# Sheet1asc2.net
KiCad netlist of a schematic drawn in Altium Designer
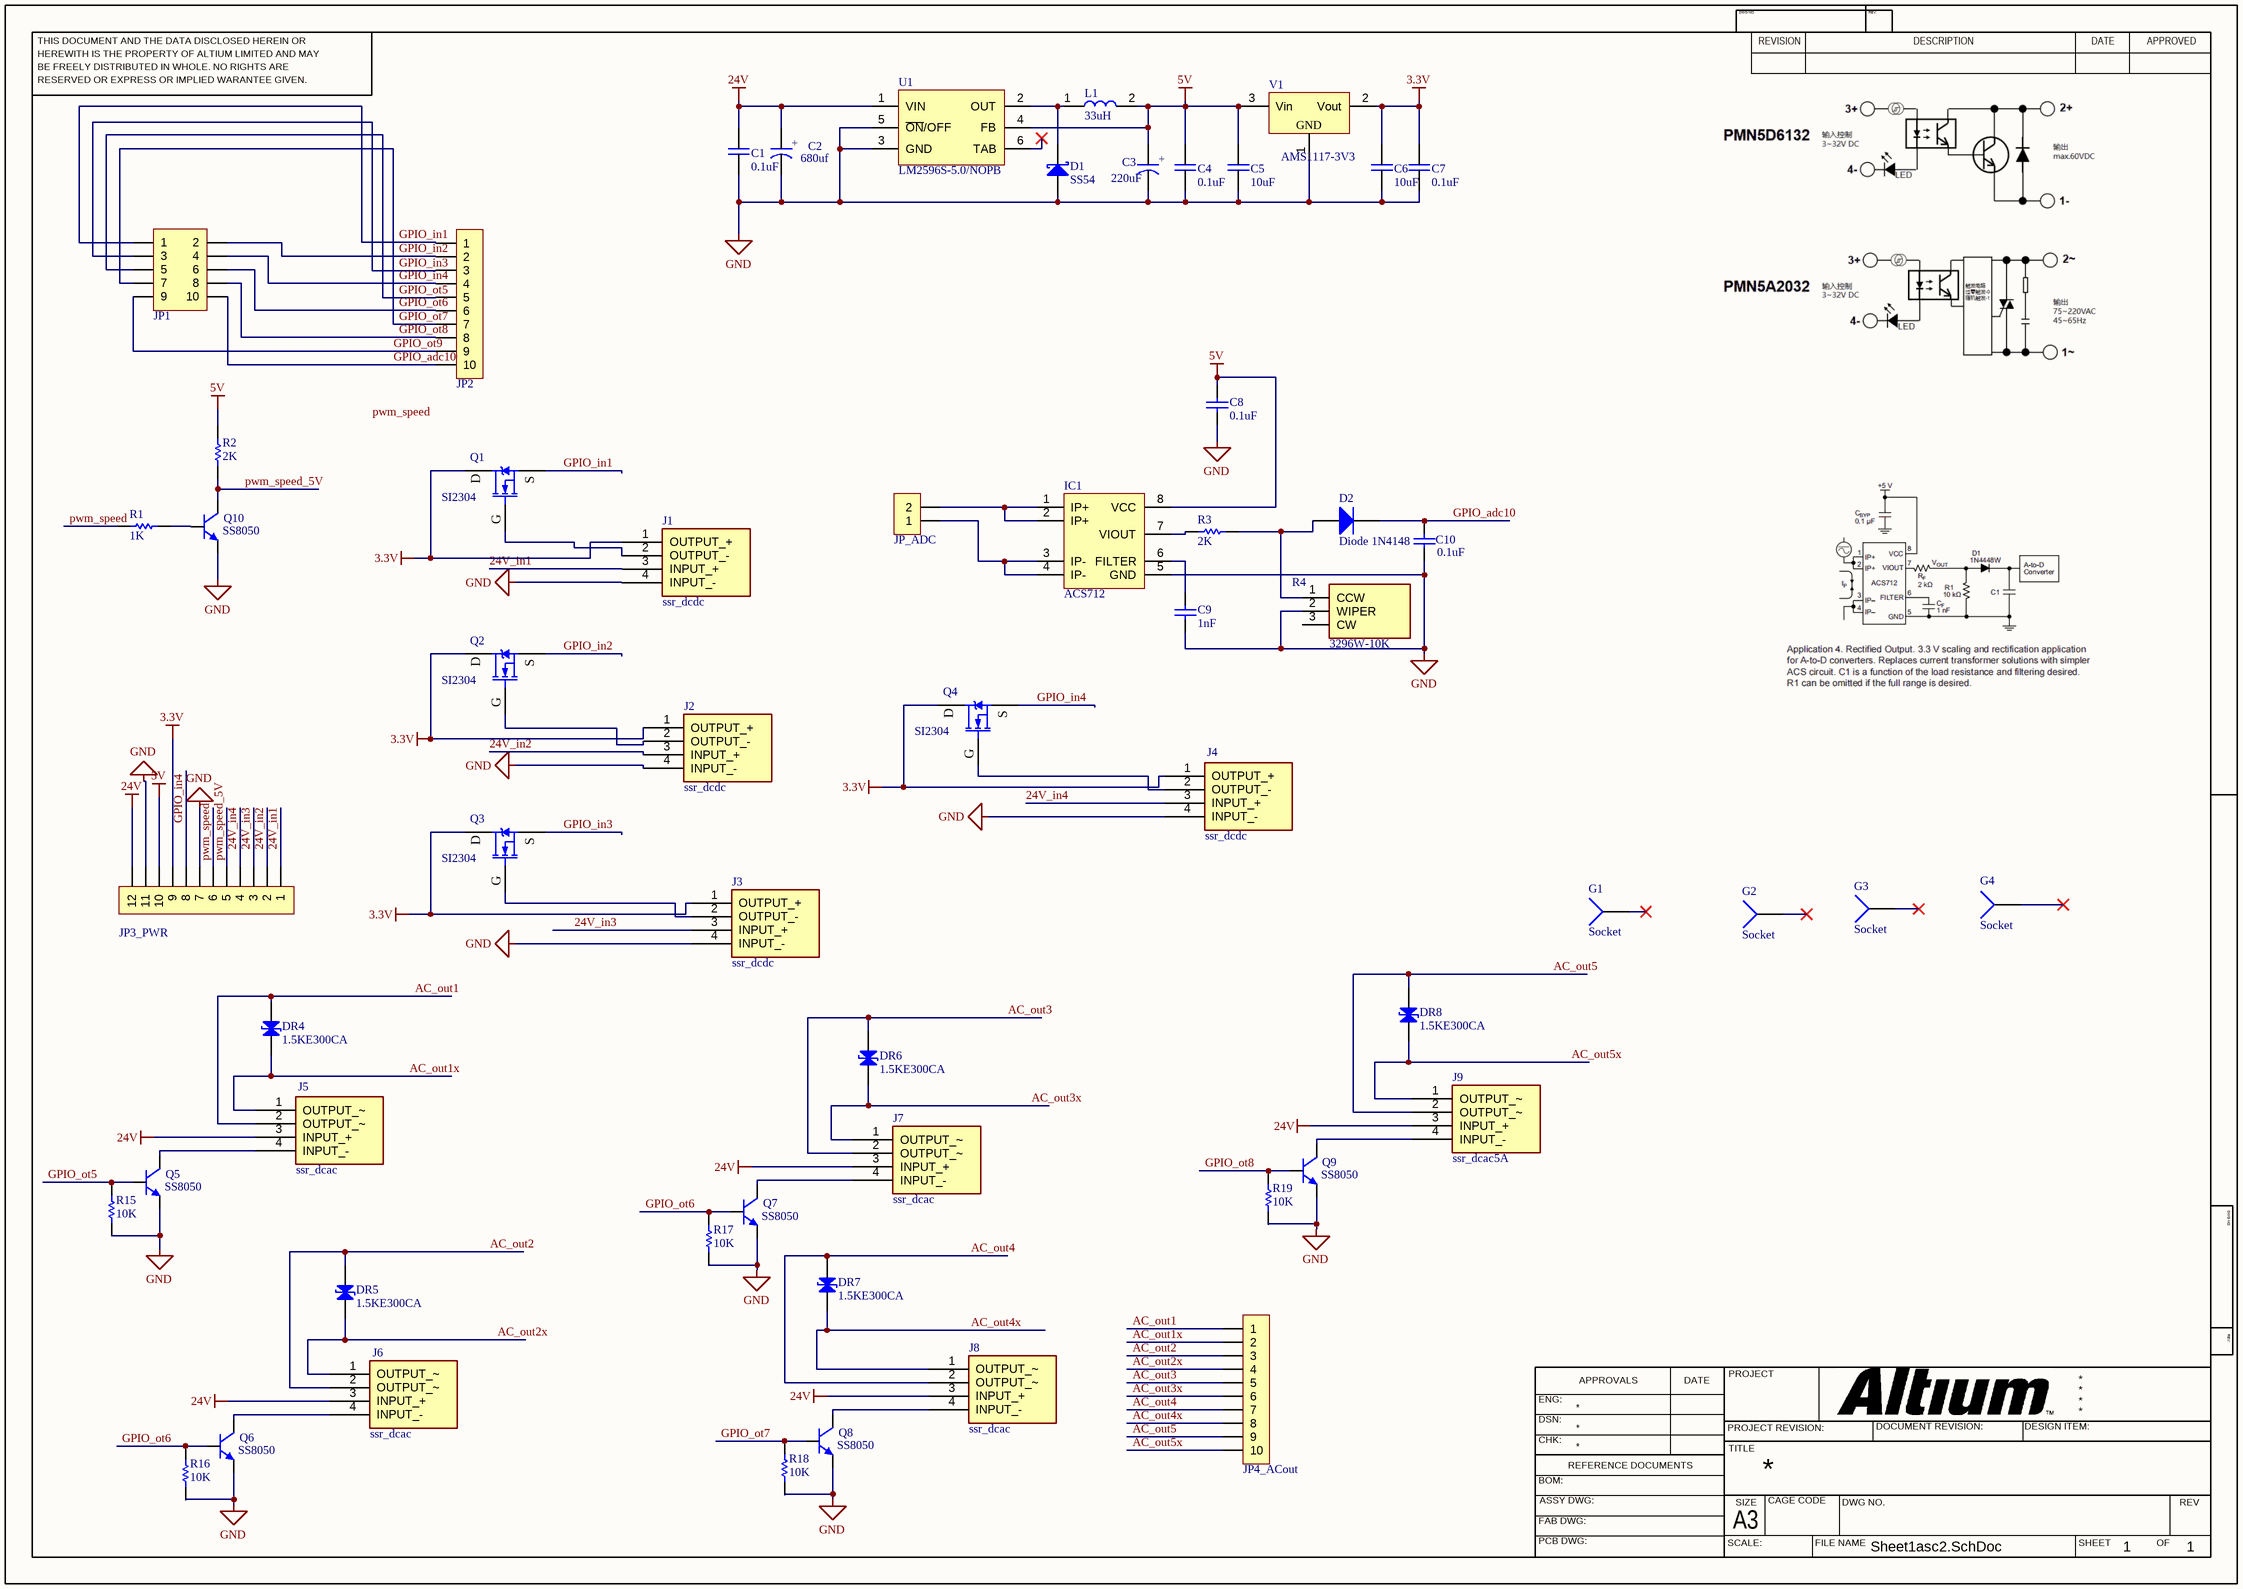
[diagram p0: Sheet1asc2.SchDoc]

(export (version "E")
  (design (tool "Eeschema 10.0.6"))
  (components
    (comp (ref "C1") (value "0.1uF") (footprint "C 0805_M") (libsource (lib "LM2596S_5.0") (part "CAP-SMT")))
    (comp (ref "C2")
      (value "680uf")
      (footprint "CAP 5.0*12.5*20")
      (description "CAP-SMD")
      (libsource (lib "LM2596S_5.0") (part "CAP-SMD"))
    )
    (comp (ref "C3")
      (value "220uF")
      (footprint "CAP 5.0*10*16")
      (description "CAP-SMD")
      (libsource (lib "LM2596S_5.0") (part "CAP-SMD"))
    )
    (comp (ref "C4") (value "0.1uF") (footprint "C 0805_M") (libsource (lib "LM2596S_5.0") (part "CAP-SMT")))
    (comp (ref "C5") (value "10uF") (footprint "C 0805_M") (libsource (lib "LM2596S_5.0") (part "CAP-SMT")))
    (comp (ref "C6") (value "10uF") (footprint "C 0805_M") (libsource (lib "LM2596S_5.0") (part "CAP-SMT")))
    (comp (ref "C7") (value "0.1uF") (footprint "C 0805_M") (libsource (lib "LM2596S_5.0") (part "CAP-SMT")))
    (comp (ref "C8")
      (value "0.1uF")
      (footprint "C 0805_M")
      (description "Capacitor")
      (fields (field (name "PUBLISHER") "Altium Limited"))
      (libsource (lib "Miscellaneous Devices") (part "Cap"))
    )
    (comp (ref "C9")
      (value "1nF")
      (footprint "C 0805_M")
      (description "Capacitor")
      (fields (field (name "PUBLISHER") "Altium Limited"))
      (libsource (lib "Miscellaneous Devices") (part "Cap"))
    )
    (comp (ref "C10")
      (value "0.1uF")
      (footprint "C 0805_M")
      (description "Capacitor")
      (fields (field (name "PUBLISHER") "Altium Limited"))
      (libsource (lib "Miscellaneous Devices") (part "Cap"))
    )
    (comp (ref "D1") (value "SS54") (footprint "SMC") (libsource (lib "LM2596S_5.0") (part "DIO")))
    (comp (ref "D2")
      (value "Diode 1N4148")
      (footprint "SOD-123")
      (description "High Conductance Fast Diode")
      (fields (field (name "PUBLISHER") "Altium Limited"))
      (libsource (lib "Miscellaneous Devices") (part "Diode 1N4148"))
    )
    (comp (ref "DR4")
      (value "1.5KE300CA")
      (footprint "SMB_L4.6-W3.6-LS5.3-BI")
      (description "瞬态电压抑制二极管")
      (fields (field (name "版权归属") "源创客"))
      (libsource (lib "8.1   - 二极管-整流桥") (part "DR"))
    )
    (comp (ref "DR5")
      (value "1.5KE300CA")
      (footprint "SMB_L4.6-W3.6-LS5.3-BI")
      (description "瞬态电压抑制二极管")
      (fields (field (name "版权归属") "源创客"))
      (libsource (lib "8.1   - 二极管-整流桥") (part "DR"))
    )
    (comp (ref "DR6")
      (value "1.5KE300CA")
      (footprint "SMB_L4.6-W3.6-LS5.3-BI")
      (description "瞬态电压抑制二极管")
      (fields (field (name "版权归属") "源创客"))
      (libsource (lib "8.1   - 二极管-整流桥") (part "DR"))
    )
    (comp (ref "DR7")
      (value "1.5KE300CA")
      (footprint "SMB_L4.6-W3.6-LS5.3-BI")
      (description "瞬态电压抑制二极管")
      (fields (field (name "版权归属") "源创客"))
      (libsource (lib "8.1   - 二极管-整流桥") (part "DR"))
    )
    (comp (ref "DR8")
      (value "1.5KE300CA")
      (footprint "SMB_L4.6-W3.6-LS5.3-BI")
      (description "瞬态电压抑制二极管")
      (fields (field (name "版权归属") "源创客"))
      (libsource (lib "8.1   - 二极管-整流桥") (part "DR"))
    )
    (comp (ref "G1")
      (value "Socket")
      (footprint "M3x6_L")
      (fields (field (name "PUBLISHER") "Altium Limited"))
      (libsource (lib "Miscellaneous Connectors") (part "Socket"))
    )
    (comp (ref "G2")
      (value "Socket")
      (footprint "M3x6_L")
      (fields (field (name "PUBLISHER") "Altium Limited"))
      (libsource (lib "Miscellaneous Connectors") (part "Socket"))
    )
    (comp (ref "G3")
      (value "Socket")
      (footprint "M3x6_L")
      (fields (field (name "PUBLISHER") "Altium Limited"))
      (libsource (lib "Miscellaneous Connectors") (part "Socket"))
    )
    (comp (ref "G4")
      (value "Socket")
      (footprint "M3x6_L")
      (fields (field (name "PUBLISHER") "Altium Limited"))
      (libsource (lib "Miscellaneous Connectors") (part "Socket"))
    )
    (comp (ref "IC1")
      (value "ACS712")
      (footprint "SOP8_M")
      (description "电流检测芯片")
      (fields (field (name "版权归属") "源创客"))
      (libsource (lib "1.1   - IC芯片") (part "ACS712"))
    )
    (comp (ref "J1")
      (value "ssr_dcdc")
      (footprint "2982647")
      (description "Connector")
      (fields
        (field (name "MANUFACTURER_PART_NUMBER") "2982647")
        (field (name "MOUSER PART NUMBER") "651-2982647")
      )
      (libsource (lib "SamacSys") (part "ssr_dcdc"))
    )
    (comp (ref "J2")
      (value "ssr_dcdc")
      (footprint "2982647")
      (description "Connector")
      (fields
        (field (name "MANUFACTURER_PART_NUMBER") "2982647")
        (field (name "MOUSER PART NUMBER") "651-2982647")
      )
      (libsource (lib "SamacSys") (part "ssr_dcdc"))
    )
    (comp (ref "J3")
      (value "ssr_dcdc")
      (footprint "2982647")
      (description "Connector")
      (fields
        (field (name "MANUFACTURER_PART_NUMBER") "2982647")
        (field (name "MOUSER PART NUMBER") "651-2982647")
      )
      (libsource (lib "SamacSys") (part "ssr_dcdc"))
    )
    (comp (ref "J4")
      (value "ssr_dcdc")
      (footprint "SamacSys:SSR_DCDC")
      (description "Connector")
      (fields
        (field (name "MANUFACTURER_PART_NUMBER") "2982647")
        (field (name "MOUSER PART NUMBER") "651-2982647")
      )
      (libsource (lib "") (part "ssr_dcdc_1"))
    )
    (comp (ref "J5")
      (value "ssr_dcac")
      (footprint "SSR_DCAC")
      (description "Connector")
      (fields
        (field (name "MANUFACTURER_PART_NUMBER") "2982647")
        (field (name "MOUSER PART NUMBER") "651-2982647")
      )
      (libsource (lib "SamacSys") (part "ssr_dcac"))
    )
    (comp (ref "J6")
      (value "ssr_dcac")
      (footprint "SSR_DCAC")
      (description "Connector")
      (fields
        (field (name "MANUFACTURER_PART_NUMBER") "2982647")
        (field (name "MOUSER PART NUMBER") "651-2982647")
      )
      (libsource (lib "SamacSys") (part "ssr_dcac"))
    )
    (comp (ref "J7")
      (value "ssr_dcac")
      (footprint "SSR_DCAC")
      (description "Connector")
      (fields
        (field (name "MANUFACTURER_PART_NUMBER") "2982647")
        (field (name "MOUSER PART NUMBER") "651-2982647")
      )
      (libsource (lib "SamacSys") (part "ssr_dcac"))
    )
    (comp (ref "J8")
      (value "ssr_dcac")
      (footprint "SSR_DCAC")
      (description "Connector")
      (fields
        (field (name "MANUFACTURER_PART_NUMBER") "2982647")
        (field (name "MOUSER PART NUMBER") "651-2982647")
      )
      (libsource (lib "SamacSys") (part "ssr_dcac"))
    )
    (comp (ref "J9")
      (value "ssr_dcac5A")
      (footprint "PMN5A/PMN5D")
      (description "Connector")
      (fields
        (field (name "MANUFACTURER_PART_NUMBER") "2982647")
        (field (name "MOUSER PART NUMBER") "651-2982647")
      )
      (libsource (lib "SamacSys") (part "ssr_dcac"))
    )
    (comp (ref "JP1")
      (value "Header 5X2")
      (footprint "IDC2.54-LI-2x5P")
      (description "5*2P接插件")
      (fields (field (name "版权归属") "源创客"))
      (libsource (lib "4.5   - 接插件-脚距2.54") (part "Header 5X2"))
    )
    (comp (ref "JP2")
      (value "HDR-1X10")
      (footprint "KF128-3.81-10P")
      (description "10P接插件")
      (fields (field (name "版权归属") "源创客"))
      (libsource (lib "4.6   - 接插件-脚距3.5") (part "Header 10"))
    )
    (comp (ref "JP3_PWR")
      (value "HDR-1X12")
      (footprint "KF128-3.81-12P")
      (description "12P接插件")
      (fields (field (name "版权归属") "源创客"))
      (libsource (lib "4.7   - 接插件-脚距3.81") (part "Header 12"))
    )
    (comp (ref "JP4_ACout")
      (value "HDR-1X10")
      (footprint "KF128-3.81-10P")
      (description "10P接插件")
      (fields (field (name "版权归属") "源创客"))
      (libsource (lib "4.6   - 接插件-脚距3.5") (part "Header 10"))
    )
    (comp (ref "JP_ADC")
      (value "HDR-1X2")
      (footprint "KF128-3.81-2P")
      (description "2P接插件")
      (fields (field (name "版权归属") "源创客"))
      (libsource (lib "4.7   - 接插件-脚距3.81") (part "Header 2"))
    )
    (comp (ref "L1") (value "33uH") (footprint "CDRH74") (libsource (lib "LM2596S_5.0") (part "L-CDRH74")))
    (comp (ref "Q1")
      (value "SI2304")
      (footprint "SOT23-3M")
      (description "N沟道场效应管")
      (fields (field (name "版权归属") "源创客"))
      (libsource (lib "6.1   - 场效应管-可控硅") (part "SI2302"))
    )
    (comp (ref "Q2")
      (value "SI2304")
      (footprint "SOT23-3M")
      (description "N沟道场效应管")
      (fields (field (name "版权归属") "源创客"))
      (libsource (lib "6.1   - 场效应管-可控硅") (part "SI2302"))
    )
    (comp (ref "Q3")
      (value "SI2304")
      (footprint "SOT23-3M")
      (description "N沟道场效应管")
      (fields (field (name "版权归属") "源创客"))
      (libsource (lib "6.1   - 场效应管-可控硅") (part "SI2302"))
    )
    (comp (ref "Q4")
      (value "SI2304")
      (footprint "SOT23-3M")
      (description "N沟道场效应管")
      (fields (field (name "版权归属") "源创客"))
      (libsource (lib "6.1   - 场效应管-可控硅") (part "SI2302"))
    )
    (comp (ref "Q5")
      (value "SS8050")
      (footprint "TO92A")
      (description "高频放大-NPN型")
      (fields (field (name "版权归属") "源创客"))
      (libsource (lib "6.2   - 三极管") (part "8050-DIP"))
    )
    (comp (ref "Q6")
      (value "SS8050")
      (footprint "TO92A")
      (description "高频放大-NPN型")
      (fields (field (name "版权归属") "源创客"))
      (libsource (lib "6.2   - 三极管") (part "8050-DIP"))
    )
    (comp (ref "Q7")
      (value "SS8050")
      (footprint "TO92A")
      (description "高频放大-NPN型")
      (fields (field (name "版权归属") "源创客"))
      (libsource (lib "6.2   - 三极管") (part "8050-DIP"))
    )
    (comp (ref "Q8")
      (value "SS8050")
      (footprint "TO92A")
      (description "高频放大-NPN型")
      (fields (field (name "版权归属") "源创客"))
      (libsource (lib "6.2   - 三极管") (part "8050-DIP"))
    )
    (comp (ref "Q9")
      (value "SS8050")
      (footprint "TO92A")
      (description "高频放大-NPN型")
      (fields (field (name "版权归属") "源创客"))
      (libsource (lib "6.2   - 三极管") (part "8050-DIP"))
    )
    (comp (ref "Q10")
      (value "SS8050")
      (footprint "TO92A")
      (description "高频放大-NPN型")
      (fields (field (name "版权归属") "源创客"))
      (libsource (lib "6.2   - 三极管") (part "8050-DIP"))
    )
    (comp (ref "R1")
      (value "1K")
      (footprint "R 0805_M")
      (description "Resistor")
      (fields (field (name "PUBLISHER") "Altium Limited"))
      (libsource (lib "Miscellaneous Devices") (part "Res1"))
    )
    (comp (ref "R2")
      (value "2K")
      (footprint "R 0805_M")
      (description "Resistor")
      (fields (field (name "PUBLISHER") "Altium Limited"))
      (libsource (lib "Miscellaneous Devices") (part "Res1"))
    )
    (comp (ref "R3")
      (value "2K")
      (footprint "R 0805_M")
      (description "Resistor")
      (fields (field (name "PUBLISHER") "Altium Limited"))
      (libsource (lib "Miscellaneous Devices") (part "Res1"))
    )
    (comp (ref "R4")
      (value "3296W-10K")
      (footprint "3296W")
      (description "Resistor")
      (fields
        (field (name "MANUFACTURER_PART_NUMBER") "3296W-1-100LF")
        (field (name "MOUSER PART NUMBER") "652-3296W-1-100LF")
      )
      (libsource (lib "*") (part "3296W-1-100LF"))
    )
    (comp (ref "R15")
      (value "10K")
      (footprint "R 0805_M")
      (description "Resistor")
      (fields (field (name "PUBLISHER") "Altium Limited"))
      (libsource (lib "Miscellaneous Devices") (part "Res1"))
    )
    (comp (ref "R16")
      (value "10K")
      (footprint "R 0805_M")
      (description "Resistor")
      (fields (field (name "PUBLISHER") "Altium Limited"))
      (libsource (lib "Miscellaneous Devices") (part "Res1"))
    )
    (comp (ref "R17")
      (value "10K")
      (footprint "R 0805_M")
      (description "Resistor")
      (fields (field (name "PUBLISHER") "Altium Limited"))
      (libsource (lib "Miscellaneous Devices") (part "Res1"))
    )
    (comp (ref "R18")
      (value "10K")
      (footprint "R 0805_M")
      (description "Resistor")
      (fields (field (name "PUBLISHER") "Altium Limited"))
      (libsource (lib "Miscellaneous Devices") (part "Res1"))
    )
    (comp (ref "R19")
      (value "10K")
      (footprint "R 0805_M")
      (description "Resistor")
      (fields (field (name "PUBLISHER") "Altium Limited"))
      (libsource (lib "Miscellaneous Devices") (part "Res1"))
    )
    (comp (ref "U1")
      (value "LM2596S-5.0/NOPB")
      (footprint "TO263-5A")
      (description "SIMPLE SWITCHER® Power Converter 150 KHz 3A Step-Down Voltage Regulator, 5-pin TO-263, Pb-Free")
      (fields (field (name "MANUFACTURER") "Texas Instruments"))
      (libsource (lib "LM2596S_5.0") (part "LM2596S-5.0"))
    )
    (comp (ref "V1")
      (value "AMS1117-3V3")
      (footprint "SOT223_M")
      (description "三端稳压芯片")
      (fields (field (name "版权归属") "源创客"))
      (libsource (lib "1.3   - 电源类芯片") (part "AMS1117"))
    )
  )
  (nets
    (net (code "1") (name "/24V_in1") (class "Default")
      (node (ref "J1") (pin "3") (pinfunction "INPUT_+_3") (pintype "passive"))
      (node (ref "JP3_PWR") (pin "1") (pinfunction "1_1") (pintype "passive"))
    )
    (net (code "2") (name "/24V_in2") (class "Default")
      (node (ref "J2") (pin "3") (pinfunction "INPUT_+_3") (pintype "passive"))
      (node (ref "JP3_PWR") (pin "2") (pinfunction "2_2") (pintype "passive"))
    )
    (net (code "3") (name "/24V_in3") (class "Default")
      (node (ref "J3") (pin "3") (pinfunction "INPUT_+_3") (pintype "passive"))
      (node (ref "JP3_PWR") (pin "3") (pinfunction "3_3") (pintype "passive"))
    )
    (net (code "4") (name "/24V_in4") (class "Default")
      (node (ref "J4") (pin "3") (pinfunction "INPUT_+_3") (pintype "passive"))
      (node (ref "JP3_PWR") (pin "4") (pinfunction "4_4") (pintype "passive"))
    )
    (net (code "5") (name "/AC_out1") (class "Default")
      (node (ref "DR4") (pin "1") (pinfunction "A_1") (pintype "passive"))
      (node (ref "J5") (pin "2") (pinfunction "OUTPUT_~_2") (pintype "passive"))
      (node (ref "JP4_ACout") (pin "1") (pinfunction "1_1") (pintype "passive"))
    )
    (net (code "6") (name "/AC_out1x") (class "Default")
      (node (ref "DR4") (pin "2") (pinfunction "K_2") (pintype "passive"))
      (node (ref "J5") (pin "1") (pinfunction "OUTPUT_~_1") (pintype "passive"))
      (node (ref "JP4_ACout") (pin "2") (pinfunction "2_2") (pintype "passive"))
    )
    (net (code "7") (name "/AC_out2") (class "Default")
      (node (ref "DR5") (pin "1") (pinfunction "A_1") (pintype "passive"))
      (node (ref "J6") (pin "2") (pinfunction "OUTPUT_~_2") (pintype "passive"))
      (node (ref "JP4_ACout") (pin "3") (pinfunction "3_3") (pintype "passive"))
    )
    (net (code "8") (name "/AC_out2x") (class "Default")
      (node (ref "DR5") (pin "2") (pinfunction "K_2") (pintype "passive"))
      (node (ref "J6") (pin "1") (pinfunction "OUTPUT_~_1") (pintype "passive"))
      (node (ref "JP4_ACout") (pin "4") (pinfunction "4_4") (pintype "passive"))
    )
    (net (code "9") (name "/AC_out3") (class "Default")
      (node (ref "DR6") (pin "1") (pinfunction "A_1") (pintype "passive"))
      (node (ref "J7") (pin "2") (pinfunction "OUTPUT_~_2") (pintype "passive"))
      (node (ref "JP4_ACout") (pin "5") (pinfunction "5_5") (pintype "passive"))
    )
    (net (code "10") (name "/AC_out3x") (class "Default")
      (node (ref "DR6") (pin "2") (pinfunction "K_2") (pintype "passive"))
      (node (ref "J7") (pin "1") (pinfunction "OUTPUT_~_1") (pintype "passive"))
      (node (ref "JP4_ACout") (pin "6") (pinfunction "6_6") (pintype "passive"))
    )
    (net (code "11") (name "/AC_out4") (class "Default")
      (node (ref "DR7") (pin "1") (pinfunction "A_1") (pintype "passive"))
      (node (ref "J8") (pin "2") (pinfunction "OUTPUT_~_2") (pintype "passive"))
      (node (ref "JP4_ACout") (pin "7") (pinfunction "7_7") (pintype "passive"))
    )
    (net (code "12") (name "/AC_out4x") (class "Default")
      (node (ref "DR7") (pin "2") (pinfunction "K_2") (pintype "passive"))
      (node (ref "J8") (pin "1") (pinfunction "OUTPUT_~_1") (pintype "passive"))
      (node (ref "JP4_ACout") (pin "8") (pinfunction "8_8") (pintype "passive"))
    )
    (net (code "13") (name "/AC_out5") (class "Default")
      (node (ref "DR8") (pin "1") (pinfunction "A_1") (pintype "passive"))
      (node (ref "J9") (pin "2") (pinfunction "OUTPUT_~_2") (pintype "passive"))
      (node (ref "JP4_ACout") (pin "9") (pinfunction "9_9") (pintype "passive"))
    )
    (net (code "14") (name "/AC_out5x") (class "Default")
      (node (ref "DR8") (pin "2") (pinfunction "K_2") (pintype "passive"))
      (node (ref "J9") (pin "1") (pinfunction "OUTPUT_~_1") (pintype "passive"))
      (node (ref "JP4_ACout") (pin "10") (pinfunction "10_10") (pintype "passive"))
    )
    (net (code "15") (name "/GPIO_adc10") (class "Default")
      (node (ref "C10") (pin "2") (pinfunction "2_2") (pintype "passive"))
      (node (ref "D2") (pin "2") (pinfunction "K_2") (pintype "passive"))
      (node (ref "JP1") (pin "10") (pinfunction "10_10") (pintype "passive"))
      (node (ref "JP2") (pin "10") (pinfunction "10_10") (pintype "passive"))
    )
    (net (code "16") (name "/GPIO_in1") (class "Default")
      (node (ref "JP1") (pin "1") (pinfunction "1_1") (pintype "passive"))
      (node (ref "JP2") (pin "1") (pinfunction "1_1") (pintype "passive"))
      (node (ref "Q1") (pin "2") (pinfunction "S_2") (pintype "passive"))
    )
    (net (code "17") (name "/GPIO_in2") (class "Default")
      (node (ref "JP1") (pin "2") (pinfunction "2_2") (pintype "passive"))
      (node (ref "JP2") (pin "2") (pinfunction "2_2") (pintype "passive"))
      (node (ref "Q2") (pin "2") (pinfunction "S_2") (pintype "passive"))
    )
    (net (code "18") (name "/GPIO_in3") (class "Default")
      (node (ref "JP1") (pin "3") (pinfunction "3_3") (pintype "passive"))
      (node (ref "JP2") (pin "3") (pinfunction "3_3") (pintype "passive"))
      (node (ref "Q3") (pin "2") (pinfunction "S_2") (pintype "passive"))
    )
    (net (code "19") (name "/GPIO_in4") (class "Default")
      (node (ref "JP1") (pin "4") (pinfunction "4_4") (pintype "passive"))
      (node (ref "JP2") (pin "4") (pinfunction "4_4") (pintype "passive"))
      (node (ref "JP3_PWR") (pin "8") (pinfunction "8_8") (pintype "passive"))
      (node (ref "Q4") (pin "2") (pinfunction "S_2") (pintype "passive"))
    )
    (net (code "20") (name "/GPIO_ot5") (class "Default")
      (node (ref "JP1") (pin "5") (pinfunction "5_5") (pintype "passive"))
      (node (ref "JP2") (pin "5") (pinfunction "5_5") (pintype "passive"))
      (node (ref "Q5") (pin "2") (pinfunction "B_2") (pintype "passive"))
      (node (ref "R15") (pin "1") (pinfunction "1_1") (pintype "passive"))
    )
    (net (code "21") (name "/GPIO_ot6") (class "Default")
      (node (ref "JP1") (pin "6") (pinfunction "6_6") (pintype "passive"))
      (node (ref "JP2") (pin "6") (pinfunction "6_6") (pintype "passive"))
      (node (ref "Q6") (pin "2") (pinfunction "B_2") (pintype "passive"))
      (node (ref "Q7") (pin "2") (pinfunction "B_2") (pintype "passive"))
      (node (ref "R16") (pin "1") (pinfunction "1_1") (pintype "passive"))
      (node (ref "R17") (pin "1") (pinfunction "1_1") (pintype "passive"))
    )
    (net (code "22") (name "/GPIO_ot7") (class "Default")
      (node (ref "JP1") (pin "7") (pinfunction "7_7") (pintype "passive"))
      (node (ref "JP2") (pin "7") (pinfunction "7_7") (pintype "passive"))
      (node (ref "Q8") (pin "2") (pinfunction "B_2") (pintype "passive"))
      (node (ref "R18") (pin "1") (pinfunction "1_1") (pintype "passive"))
    )
    (net (code "23") (name "/GPIO_ot8") (class "Default")
      (node (ref "JP1") (pin "8") (pinfunction "8_8") (pintype "passive"))
      (node (ref "JP2") (pin "8") (pinfunction "8_8") (pintype "passive"))
      (node (ref "Q9") (pin "2") (pinfunction "B_2") (pintype "passive"))
      (node (ref "R19") (pin "1") (pinfunction "1_1") (pintype "passive"))
    )
    (net (code "24") (name "/GPIO_ot9") (class "Default")
      (node (ref "JP1") (pin "9") (pinfunction "9_9") (pintype "passive"))
      (node (ref "JP2") (pin "9") (pinfunction "9_9") (pintype "passive"))
    )
    (net (code "25") (name "/pwm_speed") (class "Default")
      (node (ref "JP3_PWR") (pin "6") (pinfunction "6_6") (pintype "passive"))
      (node (ref "R1") (pin "1") (pinfunction "1_1") (pintype "passive"))
    )
    (net (code "26") (name "/pwm_speed_5V") (class "Default")
      (node (ref "JP3_PWR") (pin "5") (pinfunction "5_5") (pintype "passive"))
      (node (ref "Q10") (pin "3") (pinfunction "C_3") (pintype "passive"))
      (node (ref "R2") (pin "1") (pinfunction "1_1") (pintype "passive"))
    )
    (net (code "27") (name "3.3V") (class "Default")
      (node (ref "C6") (pin "2") (pinfunction "2_2") (pintype "passive"))
      (node (ref "C7") (pin "2") (pinfunction "2_2") (pintype "passive"))
      (node (ref "J1") (pin "1") (pinfunction "OUTPUT_+_1") (pintype "passive"))
      (node (ref "J2") (pin "1") (pinfunction "OUTPUT_+_1") (pintype "passive"))
      (node (ref "J3") (pin "1") (pinfunction "OUTPUT_+_1") (pintype "passive"))
      (node (ref "J4") (pin "1") (pinfunction "OUTPUT_+_1") (pintype "passive"))
      (node (ref "JP3_PWR") (pin "9") (pinfunction "9_9") (pintype "passive"))
      (node (ref "Q1") (pin "3") (pinfunction "D_3") (pintype "passive"))
      (node (ref "Q2") (pin "3") (pinfunction "D_3") (pintype "passive"))
      (node (ref "Q3") (pin "3") (pinfunction "D_3") (pintype "passive"))
      (node (ref "Q4") (pin "3") (pinfunction "D_3") (pintype "passive"))
      (node (ref "V1") (pin "2") (pinfunction "Vout_2") (pintype "passive"))
    )
    (net (code "28") (name "5V") (class "Default")
      (node (ref "C3") (pin "2") (pinfunction "2_2") (pintype "passive"))
      (node (ref "C4") (pin "2") (pinfunction "2_2") (pintype "passive"))
      (node (ref "C5") (pin "2") (pinfunction "2_2") (pintype "passive"))
      (node (ref "C8") (pin "2") (pinfunction "2_2") (pintype "passive"))
      (node (ref "IC1") (pin "8") (pinfunction "VCC_8") (pintype "passive"))
      (node (ref "JP3_PWR") (pin "10") (pinfunction "10_10") (pintype "passive"))
      (node (ref "L1") (pin "2") (pinfunction "2_2") (pintype "passive"))
      (node (ref "R2") (pin "2") (pinfunction "2_2") (pintype "passive"))
      (node (ref "U1") (pin "4") (pinfunction "FB_4") (pintype "passive"))
      (node (ref "V1") (pin "3") (pinfunction "Vin_3") (pintype "passive"))
    )
    (net (code "29") (name "24V") (class "Default")
      (node (ref "C1") (pin "2") (pinfunction "2_2") (pintype "passive"))
      (node (ref "C2") (pin "2") (pinfunction "2_2") (pintype "passive"))
      (node (ref "J5") (pin "3") (pinfunction "INPUT_+_3") (pintype "passive"))
      (node (ref "J6") (pin "3") (pinfunction "INPUT_+_3") (pintype "passive"))
      (node (ref "J7") (pin "3") (pinfunction "INPUT_+_3") (pintype "passive"))
      (node (ref "J8") (pin "3") (pinfunction "INPUT_+_3") (pintype "passive"))
      (node (ref "J9") (pin "3") (pinfunction "INPUT_+_3") (pintype "passive"))
      (node (ref "JP3_PWR") (pin "12") (pinfunction "12_12") (pintype "passive"))
      (node (ref "U1") (pin "1") (pinfunction "VIN_1") (pintype "power_in"))
    )
    (net (code "30") (name "GND") (class "Default")
      (node (ref "C1") (pin "1") (pinfunction "1_1") (pintype "passive"))
      (node (ref "C10") (pin "1") (pinfunction "1_1") (pintype "passive"))
      (node (ref "C2") (pin "1") (pinfunction "1_1") (pintype "passive"))
      (node (ref "C3") (pin "1") (pinfunction "1_1") (pintype "passive"))
      (node (ref "C4") (pin "1") (pinfunction "1_1") (pintype "passive"))
      (node (ref "C5") (pin "1") (pinfunction "1_1") (pintype "passive"))
      (node (ref "C6") (pin "1") (pinfunction "1_1") (pintype "passive"))
      (node (ref "C7") (pin "1") (pinfunction "1_1") (pintype "passive"))
      (node (ref "C8") (pin "1") (pinfunction "1_1") (pintype "passive"))
      (node (ref "C9") (pin "1") (pinfunction "1_1") (pintype "passive"))
      (node (ref "D1") (pin "1") (pinfunction "1_1") (pintype "passive"))
      (node (ref "IC1") (pin "5") (pinfunction "GND_5") (pintype "passive"))
      (node (ref "J1") (pin "4") (pinfunction "INPUT_-_4") (pintype "passive"))
      (node (ref "J2") (pin "4") (pinfunction "INPUT_-_4") (pintype "passive"))
      (node (ref "J3") (pin "4") (pinfunction "INPUT_-_4") (pintype "passive"))
      (node (ref "J4") (pin "4") (pinfunction "INPUT_-_4") (pintype "passive"))
      (node (ref "JP3_PWR") (pin "11") (pinfunction "11_11") (pintype "passive"))
      (node (ref "JP3_PWR") (pin "7") (pinfunction "7_7") (pintype "passive"))
      (node (ref "Q10") (pin "1") (pinfunction "E_1") (pintype "passive"))
      (node (ref "Q5") (pin "1") (pinfunction "E_1") (pintype "passive"))
      (node (ref "Q6") (pin "1") (pinfunction "E_1") (pintype "passive"))
      (node (ref "Q7") (pin "1") (pinfunction "E_1") (pintype "passive"))
      (node (ref "Q8") (pin "1") (pinfunction "E_1") (pintype "passive"))
      (node (ref "Q9") (pin "1") (pinfunction "E_1") (pintype "passive"))
      (node (ref "R15") (pin "2") (pinfunction "2_2") (pintype "passive"))
      (node (ref "R16") (pin "2") (pinfunction "2_2") (pintype "passive"))
      (node (ref "R17") (pin "2") (pinfunction "2_2") (pintype "passive"))
      (node (ref "R18") (pin "2") (pinfunction "2_2") (pintype "passive"))
      (node (ref "R19") (pin "2") (pinfunction "2_2") (pintype "passive"))
      (node (ref "R4") (pin "2") (pinfunction "WIPER_2") (pintype "passive"))
      (node (ref "U1") (pin "3") (pinfunction "GND_3") (pintype "power_in"))
      (node (ref "U1") (pin "5") (pinfunction "~{ON}/OFF_5") (pintype "passive"))
      (node (ref "V1") (pin "1") (pinfunction "GND_1") (pintype "passive"))
    )
    (net (code "31") (name "Net-(D2-A)") (class "Default")
      (node (ref "D2") (pin "1") (pinfunction "A_1") (pintype "passive"))
      (node (ref "R3") (pin "2") (pinfunction "2_2") (pintype "passive"))
      (node (ref "R4") (pin "1") (pinfunction "CCW_1") (pintype "passive"))
    )
    (net (code "32") (name "Net-(IC1-FILTER)") (class "Default")
      (node (ref "C9") (pin "2") (pinfunction "2_2") (pintype "passive"))
      (node (ref "IC1") (pin "6") (pinfunction "FILTER_6") (pintype "passive"))
    )
    (net (code "33") (name "Net-(IC1-IP+-Pad1)") (class "Default")
      (node (ref "IC1") (pin "1") (pinfunction "IP+_1") (pintype "passive"))
      (node (ref "IC1") (pin "2") (pinfunction "IP+_2") (pintype "passive"))
      (node (ref "JP_ADC") (pin "2") (pinfunction "2_2") (pintype "passive"))
    )
    (net (code "34") (name "Net-(IC1-IP--Pad3)") (class "Default")
      (node (ref "IC1") (pin "3") (pinfunction "IP-_3") (pintype "passive"))
      (node (ref "IC1") (pin "4") (pinfunction "IP-_4") (pintype "passive"))
      (node (ref "JP_ADC") (pin "1") (pinfunction "1_1") (pintype "passive"))
    )
    (net (code "35") (name "Net-(IC1-VIOUT)") (class "Default")
      (node (ref "IC1") (pin "7") (pinfunction "VIOUT_7") (pintype "passive"))
      (node (ref "R3") (pin "1") (pinfunction "1_1") (pintype "passive"))
    )
    (net (code "36") (name "Net-(J1-OUTPUT_-)") (class "Default")
      (node (ref "J1") (pin "2") (pinfunction "OUTPUT_-_2") (pintype "passive"))
      (node (ref "Q1") (pin "1") (pinfunction "G_1") (pintype "passive"))
    )
    (net (code "37") (name "Net-(J2-OUTPUT_-)") (class "Default")
      (node (ref "J2") (pin "2") (pinfunction "OUTPUT_-_2") (pintype "passive"))
      (node (ref "Q2") (pin "1") (pinfunction "G_1") (pintype "passive"))
    )
    (net (code "38") (name "Net-(J3-OUTPUT_-)") (class "Default")
      (node (ref "J3") (pin "2") (pinfunction "OUTPUT_-_2") (pintype "passive"))
      (node (ref "Q3") (pin "1") (pinfunction "G_1") (pintype "passive"))
    )
    (net (code "39") (name "Net-(J4-OUTPUT_-)") (class "Default")
      (node (ref "J4") (pin "2") (pinfunction "OUTPUT_-_2") (pintype "passive"))
      (node (ref "Q4") (pin "1") (pinfunction "G_1") (pintype "passive"))
    )
    (net (code "40") (name "Net-(J5-INPUT_-)") (class "Default")
      (node (ref "J5") (pin "4") (pinfunction "INPUT_-_4") (pintype "passive"))
      (node (ref "Q5") (pin "3") (pinfunction "C_3") (pintype "passive"))
    )
    (net (code "41") (name "Net-(J6-INPUT_-)") (class "Default")
      (node (ref "J6") (pin "4") (pinfunction "INPUT_-_4") (pintype "passive"))
      (node (ref "Q6") (pin "3") (pinfunction "C_3") (pintype "passive"))
    )
    (net (code "42") (name "Net-(J7-INPUT_-)") (class "Default")
      (node (ref "J7") (pin "4") (pinfunction "INPUT_-_4") (pintype "passive"))
      (node (ref "Q7") (pin "3") (pinfunction "C_3") (pintype "passive"))
    )
    (net (code "43") (name "Net-(J8-INPUT_-)") (class "Default")
      (node (ref "J8") (pin "4") (pinfunction "INPUT_-_4") (pintype "passive"))
      (node (ref "Q8") (pin "3") (pinfunction "C_3") (pintype "passive"))
    )
    (net (code "44") (name "Net-(J9-INPUT_-)") (class "Default")
      (node (ref "J9") (pin "4") (pinfunction "INPUT_-_4") (pintype "passive"))
      (node (ref "Q9") (pin "3") (pinfunction "C_3") (pintype "passive"))
    )
    (net (code "45") (name "Net-(Q10-B)") (class "Default")
      (node (ref "Q10") (pin "2") (pinfunction "B_2") (pintype "passive"))
      (node (ref "R1") (pin "2") (pinfunction "2_2") (pintype "passive"))
    )
    (net (code "46") (name "Net-(U1-OUT)") (class "Default")
      (node (ref "D1") (pin "2") (pinfunction "2_2") (pintype "passive"))
      (node (ref "L1") (pin "1") (pinfunction "1_1") (pintype "passive"))
      (node (ref "U1") (pin "2") (pinfunction "OUT_2") (pintype "power_in"))
    )
    (net (code "47") (name "unconnected-(G1-Pad1)") (class "Default")
      (node (ref "G1") (pin "1") (pinfunction "1_1") (pintype "passive+no_connect"))
    )
    (net (code "48") (name "unconnected-(G2-Pad1)") (class "Default")
      (node (ref "G2") (pin "1") (pinfunction "1_1") (pintype "passive+no_connect"))
    )
    (net (code "49") (name "unconnected-(G3-Pad1)") (class "Default")
      (node (ref "G3") (pin "1") (pinfunction "1_1") (pintype "passive+no_connect"))
    )
    (net (code "50") (name "unconnected-(G4-Pad1)") (class "Default")
      (node (ref "G4") (pin "1") (pinfunction "1_1") (pintype "passive+no_connect"))
    )
    (net (code "51") (name "unconnected-(R4-CW-Pad3)") (class "Default")
      (node (ref "R4") (pin "3") (pinfunction "CW_3") (pintype "passive"))
    )
    (net (code "52") (name "unconnected-(U1-TAB-Pad6)") (class "Default")
      (node (ref "U1") (pin "6") (pinfunction "TAB_6") (pintype "power_in+no_connect"))
    )
  )
)
